# SIM_slots_2.net
KiCad netlist of a schematic drawn in Altium Designer
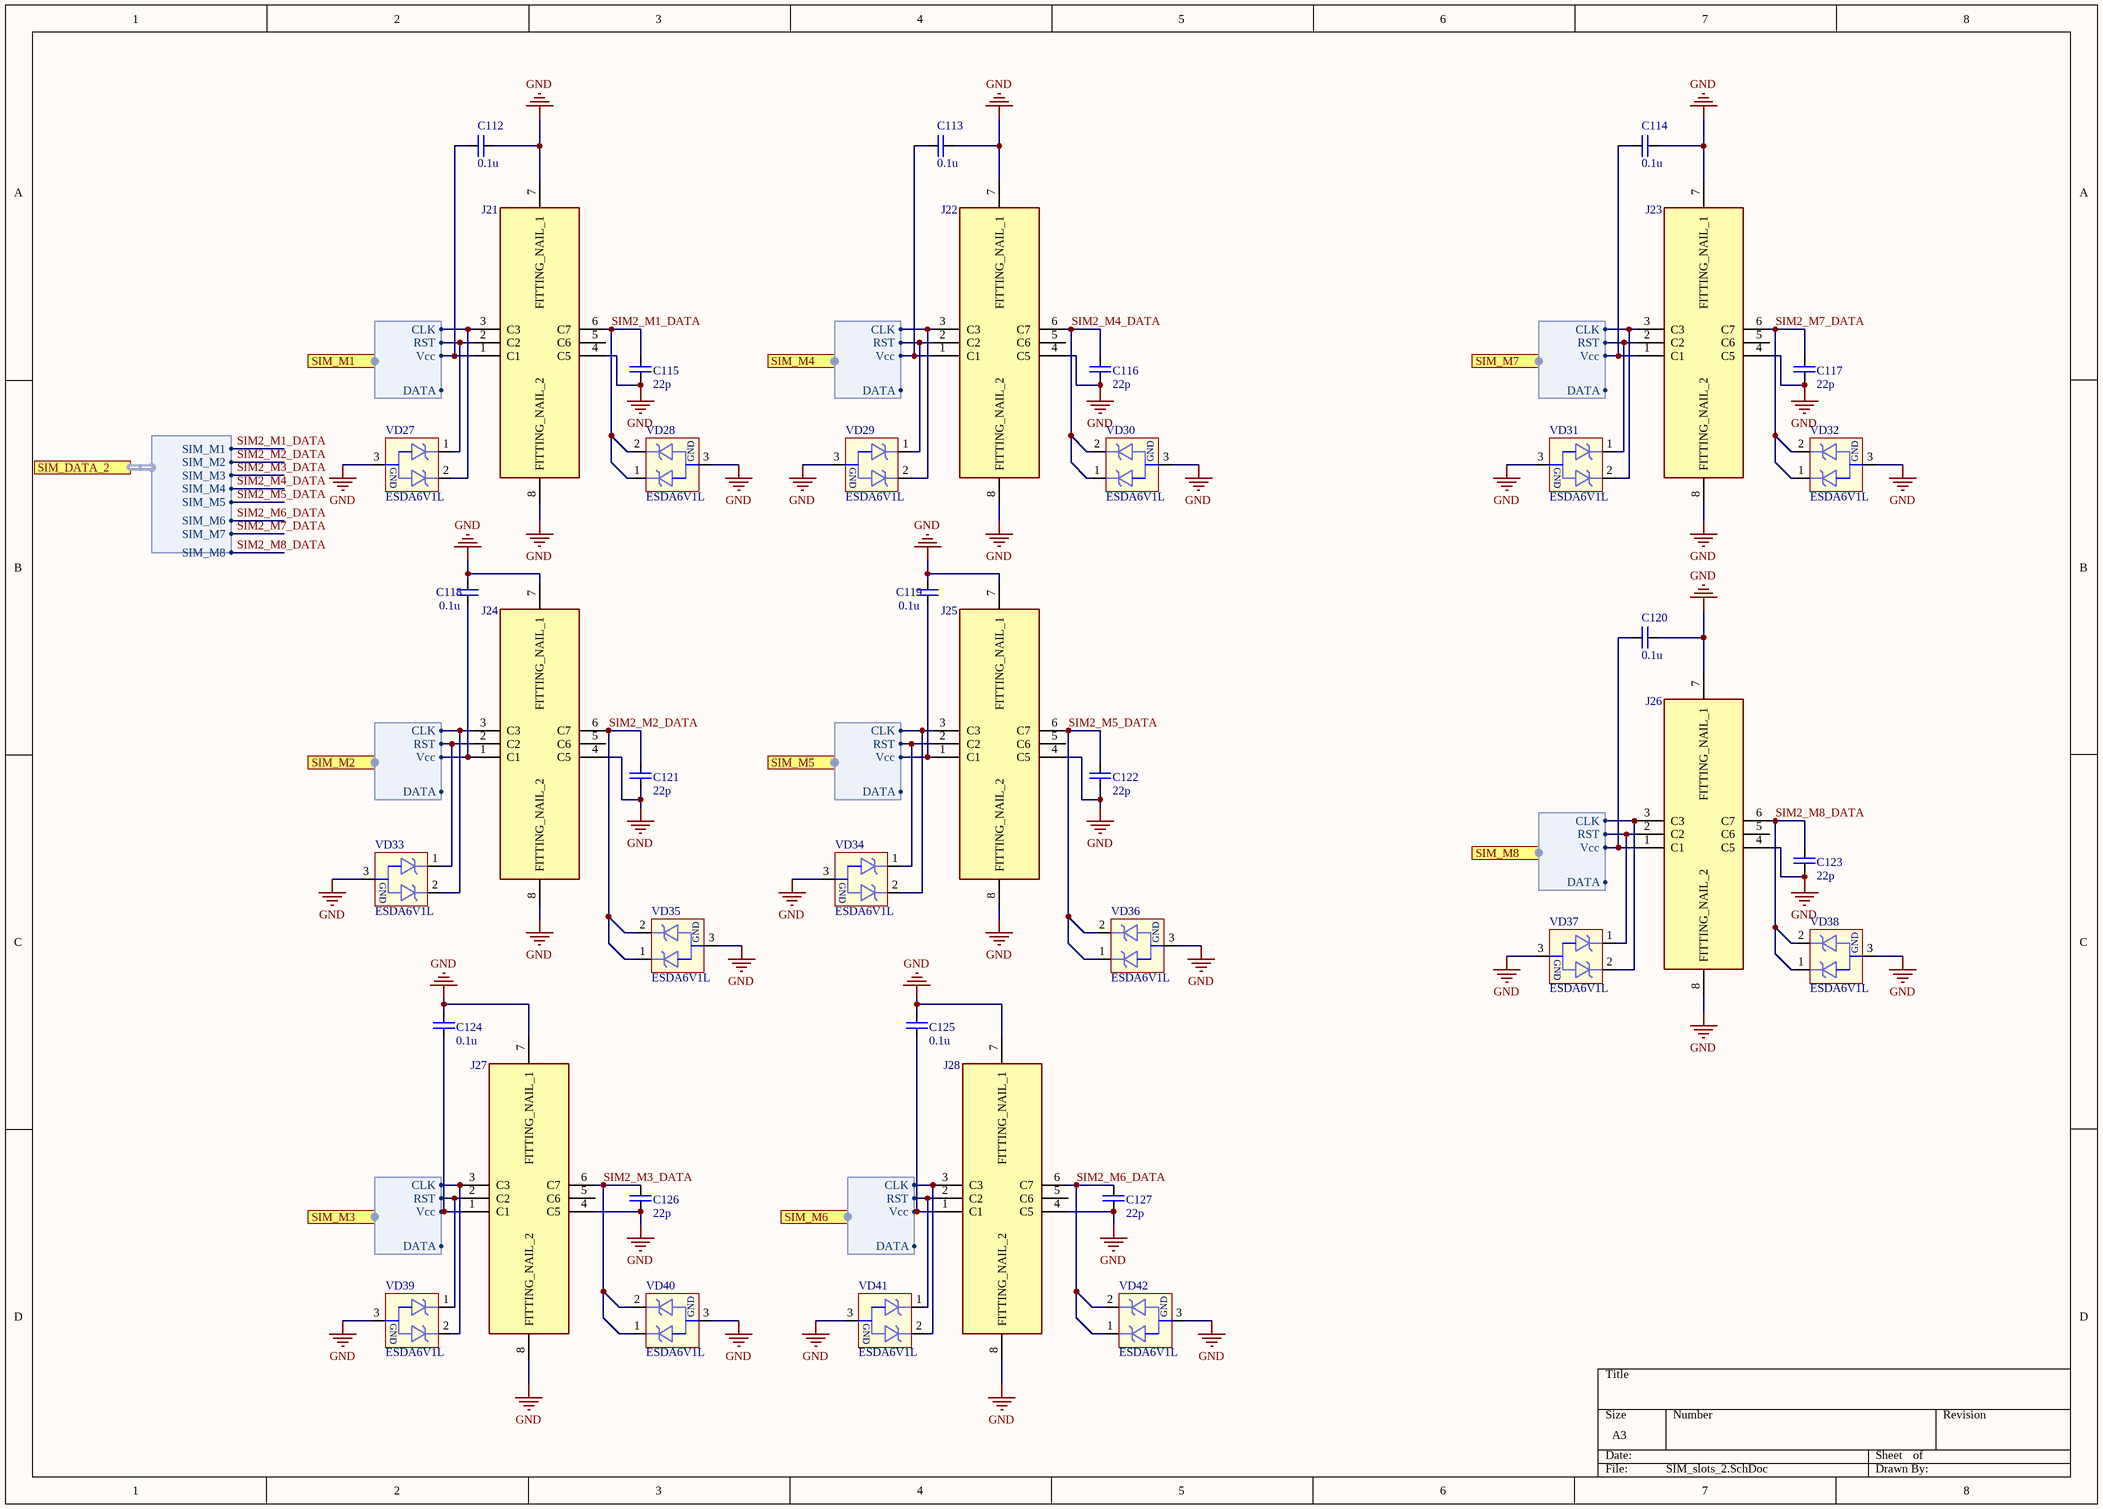
[diagram p0: SIM_slots_2.SchDoc]

(export (version "E")
  (design (tool "Eeschema 10.0.6"))
  (components
    (comp (ref "C112")
      (value "0.1u")
      (footprint "SMD_components:C0402")
      (description "Chip Capacitor 0402")
      (fields (field (name "TOLERANCE") "10%") (field (name "VOLTAGE") "25В"))
      (libsource (lib "Passives") (part "C0402"))
    )
    (comp (ref "C113")
      (value "0.1u")
      (footprint "SMD_components:C0402")
      (description "Chip Capacitor 0402")
      (fields (field (name "TOLERANCE") "10%") (field (name "VOLTAGE") "25В"))
      (libsource (lib "Passives") (part "C0402"))
    )
    (comp (ref "C114")
      (value "0.1u")
      (footprint "SMD_components:C0402")
      (description "Chip Capacitor 0402")
      (fields (field (name "TOLERANCE") "10%") (field (name "VOLTAGE") "25В"))
      (libsource (lib "Passives") (part "C0402"))
    )
    (comp (ref "C115")
      (value "22p")
      (footprint "SMD_components:C0402")
      (description "Chip Capacitor 0402")
      (fields (field (name "TOLERANCE") "10%") (field (name "VOLTAGE") "50В"))
      (libsource (lib "Passives") (part "C0402"))
    )
    (comp (ref "C116")
      (value "22p")
      (footprint "SMD_components:C0402")
      (description "Chip Capacitor 0402")
      (fields (field (name "TOLERANCE") "10%") (field (name "VOLTAGE") "50В"))
      (libsource (lib "Passives") (part "C0402"))
    )
    (comp (ref "C117")
      (value "22p")
      (footprint "SMD_components:C0402")
      (description "Chip Capacitor 0402")
      (fields (field (name "TOLERANCE") "10%") (field (name "VOLTAGE") "50В"))
      (libsource (lib "Passives") (part "C0402"))
    )
    (comp (ref "C118")
      (value "0.1u")
      (footprint "SMD_components:C0402")
      (description "Chip Capacitor 0402")
      (fields (field (name "TOLERANCE") "10%") (field (name "VOLTAGE") "25В"))
      (libsource (lib "Passives") (part "C0402"))
    )
    (comp (ref "C119")
      (value "0.1u")
      (footprint "SMD_components:C0402")
      (description "Chip Capacitor 0402")
      (fields (field (name "TOLERANCE") "10%") (field (name "VOLTAGE") "25В"))
      (libsource (lib "Passives") (part "C0402"))
    )
    (comp (ref "C120")
      (value "0.1u")
      (footprint "SMD_components:C0402")
      (description "Chip Capacitor 0402")
      (fields (field (name "TOLERANCE") "10%") (field (name "VOLTAGE") "25В"))
      (libsource (lib "Passives") (part "C0402"))
    )
    (comp (ref "C121")
      (value "22p")
      (footprint "SMD_components:C0402")
      (description "Chip Capacitor 0402")
      (fields (field (name "TOLERANCE") "10%") (field (name "VOLTAGE") "50В"))
      (libsource (lib "Passives") (part "C0402"))
    )
    (comp (ref "C122")
      (value "22p")
      (footprint "SMD_components:C0402")
      (description "Chip Capacitor 0402")
      (fields (field (name "TOLERANCE") "10%") (field (name "VOLTAGE") "50В"))
      (libsource (lib "Passives") (part "C0402"))
    )
    (comp (ref "C123")
      (value "22p")
      (footprint "SMD_components:C0402")
      (description "Chip Capacitor 0402")
      (fields (field (name "TOLERANCE") "10%") (field (name "VOLTAGE") "50В"))
      (libsource (lib "Passives") (part "C0402"))
    )
    (comp (ref "C124")
      (value "0.1u")
      (footprint "SMD_components:C0402")
      (description "Chip Capacitor 0402")
      (fields (field (name "TOLERANCE") "10%") (field (name "VOLTAGE") "25В"))
      (libsource (lib "Passives") (part "C0402"))
    )
    (comp (ref "C125")
      (value "0.1u")
      (footprint "SMD_components:C0402")
      (description "Chip Capacitor 0402")
      (fields (field (name "TOLERANCE") "10%") (field (name "VOLTAGE") "25В"))
      (libsource (lib "Passives") (part "C0402"))
    )
    (comp (ref "C126")
      (value "22p")
      (footprint "SMD_components:C0402")
      (description "Chip Capacitor 0402")
      (fields (field (name "TOLERANCE") "10%") (field (name "VOLTAGE") "50В"))
      (libsource (lib "Passives") (part "C0402"))
    )
    (comp (ref "C127")
      (value "22p")
      (footprint "SMD_components:C0402")
      (description "Chip Capacitor 0402")
      (fields (field (name "TOLERANCE") "10%") (field (name "VOLTAGE") "50В"))
      (libsource (lib "Passives") (part "C0402"))
    )
    (comp (ref "J21")
      (value "47388-2001")
      (footprint "473882001")
      (description "Connector")
      (fields (field (name "MOUSER PART NUMBER") "538-47388-2001"))
      (libsource (lib "Connectors") (part "47388-2001"))
    )
    (comp (ref "J22")
      (value "47388-2001")
      (footprint "473882001")
      (description "Connector")
      (fields (field (name "MOUSER PART NUMBER") "538-47388-2001"))
      (libsource (lib "Connectors") (part "47388-2001"))
    )
    (comp (ref "J23")
      (value "47388-2001")
      (footprint "473882001")
      (description "Connector")
      (fields (field (name "MOUSER PART NUMBER") "538-47388-2001"))
      (libsource (lib "Connectors") (part "47388-2001"))
    )
    (comp (ref "J24")
      (value "47388-2001")
      (footprint "473882001")
      (description "Connector")
      (fields (field (name "MOUSER PART NUMBER") "538-47388-2001"))
      (libsource (lib "Connectors") (part "47388-2001"))
    )
    (comp (ref "J25")
      (value "47388-2001")
      (footprint "473882001")
      (description "Connector")
      (fields (field (name "MOUSER PART NUMBER") "538-47388-2001"))
      (libsource (lib "Connectors") (part "47388-2001"))
    )
    (comp (ref "J26")
      (value "47388-2001")
      (footprint "473882001")
      (description "Connector")
      (fields (field (name "MOUSER PART NUMBER") "538-47388-2001"))
      (libsource (lib "Connectors") (part "47388-2001"))
    )
    (comp (ref "J27")
      (value "47388-2001")
      (footprint "473882001")
      (description "Connector")
      (fields (field (name "MOUSER PART NUMBER") "538-47388-2001"))
      (libsource (lib "Connectors") (part "47388-2001"))
    )
    (comp (ref "J28")
      (value "47388-2001")
      (footprint "473882001")
      (description "Connector")
      (fields (field (name "MOUSER PART NUMBER") "538-47388-2001"))
      (libsource (lib "Connectors") (part "47388-2001"))
    )
    (comp (ref "VD27")
      (value "Диод защитный, ESDA6V1L")
      (footprint "SMD_components:SOT23-3L")
      (description "Dual diode array for ESD protection")
      (fields (field (name "MANUFACTURER") "STMicroelectronics") (field (name "PARTNUMBER") "ESDA6V1L"))
      (libsource (lib "Discrete") (part "ESDA6V1L"))
    )
    (comp (ref "VD28")
      (value "Диод защитный, ESDA6V1L")
      (footprint "SMD_components:SOT23-3L")
      (description "Dual diode array for ESD protection")
      (fields (field (name "MANUFACTURER") "STMicroelectronics") (field (name "PARTNUMBER") "ESDA6V1L"))
      (libsource (lib "") (part "ESDA6V1L_1"))
    )
    (comp (ref "VD29")
      (value "Диод защитный, ESDA6V1L")
      (footprint "SMD_components:SOT23-3L")
      (description "Dual diode array for ESD protection")
      (fields (field (name "MANUFACTURER") "STMicroelectronics") (field (name "PARTNUMBER") "ESDA6V1L"))
      (libsource (lib "Discrete") (part "ESDA6V1L"))
    )
    (comp (ref "VD30")
      (value "Диод защитный, ESDA6V1L")
      (footprint "SMD_components:SOT23-3L")
      (description "Dual diode array for ESD protection")
      (fields (field (name "MANUFACTURER") "STMicroelectronics") (field (name "PARTNUMBER") "ESDA6V1L"))
      (libsource (lib "") (part "ESDA6V1L_1"))
    )
    (comp (ref "VD31")
      (value "Диод защитный, ESDA6V1L")
      (footprint "SMD_components:SOT23-3L")
      (description "Dual diode array for ESD protection")
      (fields (field (name "MANUFACTURER") "STMicroelectronics") (field (name "PARTNUMBER") "ESDA6V1L"))
      (libsource (lib "Discrete") (part "ESDA6V1L"))
    )
    (comp (ref "VD32")
      (value "Диод защитный, ESDA6V1L")
      (footprint "SMD_components:SOT23-3L")
      (description "Dual diode array for ESD protection")
      (fields (field (name "MANUFACTURER") "STMicroelectronics") (field (name "PARTNUMBER") "ESDA6V1L"))
      (libsource (lib "") (part "ESDA6V1L_1"))
    )
    (comp (ref "VD33")
      (value "Диод защитный, ESDA6V1L")
      (footprint "SMD_components:SOT23-3L")
      (description "Dual diode array for ESD protection")
      (fields (field (name "MANUFACTURER") "STMicroelectronics") (field (name "PARTNUMBER") "ESDA6V1L"))
      (libsource (lib "Discrete") (part "ESDA6V1L"))
    )
    (comp (ref "VD34")
      (value "Диод защитный, ESDA6V1L")
      (footprint "SMD_components:SOT23-3L")
      (description "Dual diode array for ESD protection")
      (fields (field (name "MANUFACTURER") "STMicroelectronics") (field (name "PARTNUMBER") "ESDA6V1L"))
      (libsource (lib "Discrete") (part "ESDA6V1L"))
    )
    (comp (ref "VD35")
      (value "Диод защитный, ESDA6V1L")
      (footprint "SMD_components:SOT23-3L")
      (description "Dual diode array for ESD protection")
      (fields (field (name "MANUFACTURER") "STMicroelectronics") (field (name "PARTNUMBER") "ESDA6V1L"))
      (libsource (lib "") (part "ESDA6V1L_1"))
    )
    (comp (ref "VD36")
      (value "Диод защитный, ESDA6V1L")
      (footprint "SMD_components:SOT23-3L")
      (description "Dual diode array for ESD protection")
      (fields (field (name "MANUFACTURER") "STMicroelectronics") (field (name "PARTNUMBER") "ESDA6V1L"))
      (libsource (lib "") (part "ESDA6V1L_1"))
    )
    (comp (ref "VD37")
      (value "Диод защитный, ESDA6V1L")
      (footprint "SMD_components:SOT23-3L")
      (description "Dual diode array for ESD protection")
      (fields (field (name "MANUFACTURER") "STMicroelectronics") (field (name "PARTNUMBER") "ESDA6V1L"))
      (libsource (lib "Discrete") (part "ESDA6V1L"))
    )
    (comp (ref "VD38")
      (value "Диод защитный, ESDA6V1L")
      (footprint "SMD_components:SOT23-3L")
      (description "Dual diode array for ESD protection")
      (fields (field (name "MANUFACTURER") "STMicroelectronics") (field (name "PARTNUMBER") "ESDA6V1L"))
      (libsource (lib "") (part "ESDA6V1L_1"))
    )
    (comp (ref "VD39")
      (value "Диод защитный, ESDA6V1L")
      (footprint "SMD_components:SOT23-3L")
      (description "Dual diode array for ESD protection")
      (fields (field (name "MANUFACTURER") "STMicroelectronics") (field (name "PARTNUMBER") "ESDA6V1L"))
      (libsource (lib "Discrete") (part "ESDA6V1L"))
    )
    (comp (ref "VD40")
      (value "Диод защитный, ESDA6V1L")
      (footprint "SMD_components:SOT23-3L")
      (description "Dual diode array for ESD protection")
      (fields (field (name "MANUFACTURER") "STMicroelectronics") (field (name "PARTNUMBER") "ESDA6V1L"))
      (libsource (lib "") (part "ESDA6V1L_1"))
    )
    (comp (ref "VD41")
      (value "Диод защитный, ESDA6V1L")
      (footprint "SMD_components:SOT23-3L")
      (description "Dual diode array for ESD protection")
      (fields (field (name "MANUFACTURER") "STMicroelectronics") (field (name "PARTNUMBER") "ESDA6V1L"))
      (libsource (lib "Discrete") (part "ESDA6V1L"))
    )
    (comp (ref "VD42")
      (value "Диод защитный, ESDA6V1L")
      (footprint "SMD_components:SOT23-3L")
      (description "Dual diode array for ESD protection")
      (fields (field (name "MANUFACTURER") "STMicroelectronics") (field (name "PARTNUMBER") "ESDA6V1L"))
      (libsource (lib "") (part "ESDA6V1L_1"))
    )
  )
  (nets
    (net (code "3") (name "/SIM2_M1_DATA") (class "Default")
      (node (ref "C115") (pin "2") (pinfunction "2_2") (pintype "passive"))
      (node (ref "J21") (pin "6") (pinfunction "C7_6") (pintype "passive"))
      (node (ref "VD28") (pin "1") (pinfunction "1_1") (pintype "passive"))
      (node (ref "VD28") (pin "2") (pinfunction "2_2") (pintype "passive"))
    )
    (net (code "4") (name "/SIM2_M2_DATA") (class "Default")
      (node (ref "C121") (pin "2") (pinfunction "2_2") (pintype "passive"))
      (node (ref "J24") (pin "6") (pinfunction "C7_6") (pintype "passive"))
      (node (ref "VD35") (pin "1") (pinfunction "1_1") (pintype "passive"))
      (node (ref "VD35") (pin "2") (pinfunction "2_2") (pintype "passive"))
    )
    (net (code "5") (name "/SIM2_M3_DATA") (class "Default")
      (node (ref "C126") (pin "2") (pinfunction "2_2") (pintype "passive"))
      (node (ref "J27") (pin "6") (pinfunction "C7_6") (pintype "passive"))
      (node (ref "VD40") (pin "1") (pinfunction "1_1") (pintype "passive"))
      (node (ref "VD40") (pin "2") (pinfunction "2_2") (pintype "passive"))
    )
    (net (code "6") (name "/SIM2_M4_DATA") (class "Default")
      (node (ref "C116") (pin "2") (pinfunction "2_2") (pintype "passive"))
      (node (ref "J22") (pin "6") (pinfunction "C7_6") (pintype "passive"))
      (node (ref "VD30") (pin "1") (pinfunction "1_1") (pintype "passive"))
      (node (ref "VD30") (pin "2") (pinfunction "2_2") (pintype "passive"))
    )
    (net (code "7") (name "/SIM2_M5_DATA") (class "Default")
      (node (ref "C122") (pin "2") (pinfunction "2_2") (pintype "passive"))
      (node (ref "J25") (pin "6") (pinfunction "C7_6") (pintype "passive"))
      (node (ref "VD36") (pin "1") (pinfunction "1_1") (pintype "passive"))
      (node (ref "VD36") (pin "2") (pinfunction "2_2") (pintype "passive"))
    )
    (net (code "8") (name "/SIM2_M6_DATA") (class "Default")
      (node (ref "C127") (pin "2") (pinfunction "2_2") (pintype "passive"))
      (node (ref "J28") (pin "6") (pinfunction "C7_6") (pintype "passive"))
      (node (ref "VD42") (pin "1") (pinfunction "1_1") (pintype "passive"))
      (node (ref "VD42") (pin "2") (pinfunction "2_2") (pintype "passive"))
    )
    (net (code "9") (name "/SIM2_M7_DATA") (class "Default")
      (node (ref "C117") (pin "2") (pinfunction "2_2") (pintype "passive"))
      (node (ref "J23") (pin "6") (pinfunction "C7_6") (pintype "passive"))
      (node (ref "VD32") (pin "1") (pinfunction "1_1") (pintype "passive"))
      (node (ref "VD32") (pin "2") (pinfunction "2_2") (pintype "passive"))
    )
    (net (code "10") (name "/SIM2_M8_DATA") (class "Default")
      (node (ref "C123") (pin "2") (pinfunction "2_2") (pintype "passive"))
      (node (ref "J26") (pin "6") (pinfunction "C7_6") (pintype "passive"))
      (node (ref "VD38") (pin "1") (pinfunction "1_1") (pintype "passive"))
      (node (ref "VD38") (pin "2") (pinfunction "2_2") (pintype "passive"))
    )
    (net (code "13") (name "GND") (class "Default")
      (node (ref "C112") (pin "2") (pinfunction "2_2") (pintype "passive"))
      (node (ref "C113") (pin "2") (pinfunction "2_2") (pintype "passive"))
      (node (ref "C114") (pin "2") (pinfunction "2_2") (pintype "passive"))
      (node (ref "C115") (pin "1") (pinfunction "1_1") (pintype "passive"))
      (node (ref "C116") (pin "1") (pinfunction "1_1") (pintype "passive"))
      (node (ref "C117") (pin "1") (pinfunction "1_1") (pintype "passive"))
      (node (ref "C118") (pin "2") (pinfunction "2_2") (pintype "passive"))
      (node (ref "C119") (pin "2") (pinfunction "2_2") (pintype "passive"))
      (node (ref "C120") (pin "2") (pinfunction "2_2") (pintype "passive"))
      (node (ref "C121") (pin "1") (pinfunction "1_1") (pintype "passive"))
      (node (ref "C122") (pin "1") (pinfunction "1_1") (pintype "passive"))
      (node (ref "C123") (pin "1") (pinfunction "1_1") (pintype "passive"))
      (node (ref "C124") (pin "2") (pinfunction "2_2") (pintype "passive"))
      (node (ref "C125") (pin "2") (pinfunction "2_2") (pintype "passive"))
      (node (ref "C126") (pin "1") (pinfunction "1_1") (pintype "passive"))
      (node (ref "C127") (pin "1") (pinfunction "1_1") (pintype "passive"))
      (node (ref "J21") (pin "4") (pinfunction "C5_4") (pintype "passive"))
      (node (ref "J21") (pin "7") (pinfunction "FITTING_NAIL_1_7") (pintype "passive"))
      (node (ref "J21") (pin "8") (pinfunction "FITTING_NAIL_2_8") (pintype "passive"))
      (node (ref "J22") (pin "4") (pinfunction "C5_4") (pintype "passive"))
      (node (ref "J22") (pin "7") (pinfunction "FITTING_NAIL_1_7") (pintype "passive"))
      (node (ref "J22") (pin "8") (pinfunction "FITTING_NAIL_2_8") (pintype "passive"))
      (node (ref "J23") (pin "4") (pinfunction "C5_4") (pintype "passive"))
      (node (ref "J23") (pin "7") (pinfunction "FITTING_NAIL_1_7") (pintype "passive"))
      (node (ref "J23") (pin "8") (pinfunction "FITTING_NAIL_2_8") (pintype "passive"))
      (node (ref "J24") (pin "4") (pinfunction "C5_4") (pintype "passive"))
      (node (ref "J24") (pin "7") (pinfunction "FITTING_NAIL_1_7") (pintype "passive"))
      (node (ref "J24") (pin "8") (pinfunction "FITTING_NAIL_2_8") (pintype "passive"))
      (node (ref "J25") (pin "4") (pinfunction "C5_4") (pintype "passive"))
      (node (ref "J25") (pin "7") (pinfunction "FITTING_NAIL_1_7") (pintype "passive"))
      (node (ref "J25") (pin "8") (pinfunction "FITTING_NAIL_2_8") (pintype "passive"))
      (node (ref "J26") (pin "4") (pinfunction "C5_4") (pintype "passive"))
      (node (ref "J26") (pin "7") (pinfunction "FITTING_NAIL_1_7") (pintype "passive"))
      (node (ref "J26") (pin "8") (pinfunction "FITTING_NAIL_2_8") (pintype "passive"))
      (node (ref "J27") (pin "4") (pinfunction "C5_4") (pintype "passive"))
      (node (ref "J27") (pin "7") (pinfunction "FITTING_NAIL_1_7") (pintype "passive"))
      (node (ref "J27") (pin "8") (pinfunction "FITTING_NAIL_2_8") (pintype "passive"))
      (node (ref "J28") (pin "4") (pinfunction "C5_4") (pintype "passive"))
      (node (ref "J28") (pin "7") (pinfunction "FITTING_NAIL_1_7") (pintype "passive"))
      (node (ref "J28") (pin "8") (pinfunction "FITTING_NAIL_2_8") (pintype "passive"))
      (node (ref "VD27") (pin "3") (pinfunction "GND_3") (pintype "passive"))
      (node (ref "VD28") (pin "3") (pinfunction "GND_3") (pintype "passive"))
      (node (ref "VD29") (pin "3") (pinfunction "GND_3") (pintype "passive"))
      (node (ref "VD30") (pin "3") (pinfunction "GND_3") (pintype "passive"))
      (node (ref "VD31") (pin "3") (pinfunction "GND_3") (pintype "passive"))
      (node (ref "VD32") (pin "3") (pinfunction "GND_3") (pintype "passive"))
      (node (ref "VD33") (pin "3") (pinfunction "GND_3") (pintype "passive"))
      (node (ref "VD34") (pin "3") (pinfunction "GND_3") (pintype "passive"))
      (node (ref "VD35") (pin "3") (pinfunction "GND_3") (pintype "passive"))
      (node (ref "VD36") (pin "3") (pinfunction "GND_3") (pintype "passive"))
      (node (ref "VD37") (pin "3") (pinfunction "GND_3") (pintype "passive"))
      (node (ref "VD38") (pin "3") (pinfunction "GND_3") (pintype "passive"))
      (node (ref "VD39") (pin "3") (pinfunction "GND_3") (pintype "passive"))
      (node (ref "VD40") (pin "3") (pinfunction "GND_3") (pintype "passive"))
      (node (ref "VD41") (pin "3") (pinfunction "GND_3") (pintype "passive"))
      (node (ref "VD42") (pin "3") (pinfunction "GND_3") (pintype "passive"))
    )
    (net (code "14") (name "Net-(J21-C1)") (class "Default")
      (node (ref "C112") (pin "1") (pinfunction "1_1") (pintype "passive"))
      (node (ref "J21") (pin "1") (pinfunction "C1_1") (pintype "passive"))
    )
    (net (code "15") (name "Net-(J21-C2)") (class "Default")
      (node (ref "J21") (pin "2") (pinfunction "C2_2") (pintype "passive"))
      (node (ref "VD27") (pin "1") (pinfunction "1_1") (pintype "passive"))
    )
    (net (code "16") (name "Net-(J21-C3)") (class "Default")
      (node (ref "J21") (pin "3") (pinfunction "C3_3") (pintype "passive"))
      (node (ref "VD27") (pin "2") (pinfunction "2_2") (pintype "passive"))
    )
    (net (code "17") (name "Net-(J22-C1)") (class "Default")
      (node (ref "C113") (pin "1") (pinfunction "1_1") (pintype "passive"))
      (node (ref "J22") (pin "1") (pinfunction "C1_1") (pintype "passive"))
    )
    (net (code "18") (name "Net-(J22-C2)") (class "Default")
      (node (ref "J22") (pin "2") (pinfunction "C2_2") (pintype "passive"))
      (node (ref "VD29") (pin "1") (pinfunction "1_1") (pintype "passive"))
    )
    (net (code "19") (name "Net-(J22-C3)") (class "Default")
      (node (ref "J22") (pin "3") (pinfunction "C3_3") (pintype "passive"))
      (node (ref "VD29") (pin "2") (pinfunction "2_2") (pintype "passive"))
    )
    (net (code "20") (name "Net-(J23-C1)") (class "Default")
      (node (ref "C114") (pin "1") (pinfunction "1_1") (pintype "passive"))
      (node (ref "J23") (pin "1") (pinfunction "C1_1") (pintype "passive"))
    )
    (net (code "21") (name "Net-(J23-C2)") (class "Default")
      (node (ref "J23") (pin "2") (pinfunction "C2_2") (pintype "passive"))
      (node (ref "VD31") (pin "1") (pinfunction "1_1") (pintype "passive"))
    )
    (net (code "22") (name "Net-(J23-C3)") (class "Default")
      (node (ref "J23") (pin "3") (pinfunction "C3_3") (pintype "passive"))
      (node (ref "VD31") (pin "2") (pinfunction "2_2") (pintype "passive"))
    )
    (net (code "23") (name "Net-(J24-C1)") (class "Default")
      (node (ref "C118") (pin "1") (pinfunction "1_1") (pintype "passive"))
      (node (ref "J24") (pin "1") (pinfunction "C1_1") (pintype "passive"))
    )
    (net (code "24") (name "Net-(J24-C2)") (class "Default")
      (node (ref "J24") (pin "2") (pinfunction "C2_2") (pintype "passive"))
      (node (ref "VD33") (pin "1") (pinfunction "1_1") (pintype "passive"))
    )
    (net (code "25") (name "Net-(J24-C3)") (class "Default")
      (node (ref "J24") (pin "3") (pinfunction "C3_3") (pintype "passive"))
      (node (ref "VD33") (pin "2") (pinfunction "2_2") (pintype "passive"))
    )
    (net (code "26") (name "Net-(J25-C1)") (class "Default")
      (node (ref "C119") (pin "1") (pinfunction "1_1") (pintype "passive"))
      (node (ref "J25") (pin "1") (pinfunction "C1_1") (pintype "passive"))
    )
    (net (code "27") (name "Net-(J25-C2)") (class "Default")
      (node (ref "J25") (pin "2") (pinfunction "C2_2") (pintype "passive"))
      (node (ref "VD34") (pin "1") (pinfunction "1_1") (pintype "passive"))
    )
    (net (code "28") (name "Net-(J25-C3)") (class "Default")
      (node (ref "J25") (pin "3") (pinfunction "C3_3") (pintype "passive"))
      (node (ref "VD34") (pin "2") (pinfunction "2_2") (pintype "passive"))
    )
    (net (code "29") (name "Net-(J26-C1)") (class "Default")
      (node (ref "C120") (pin "1") (pinfunction "1_1") (pintype "passive"))
      (node (ref "J26") (pin "1") (pinfunction "C1_1") (pintype "passive"))
    )
    (net (code "30") (name "Net-(J26-C2)") (class "Default")
      (node (ref "J26") (pin "2") (pinfunction "C2_2") (pintype "passive"))
      (node (ref "VD37") (pin "1") (pinfunction "1_1") (pintype "passive"))
    )
    (net (code "31") (name "Net-(J26-C3)") (class "Default")
      (node (ref "J26") (pin "3") (pinfunction "C3_3") (pintype "passive"))
      (node (ref "VD37") (pin "2") (pinfunction "2_2") (pintype "passive"))
    )
    (net (code "32") (name "Net-(J27-C1)") (class "Default")
      (node (ref "C124") (pin "1") (pinfunction "1_1") (pintype "passive"))
      (node (ref "J27") (pin "1") (pinfunction "C1_1") (pintype "passive"))
    )
    (net (code "33") (name "Net-(J27-C2)") (class "Default")
      (node (ref "J27") (pin "2") (pinfunction "C2_2") (pintype "passive"))
      (node (ref "VD39") (pin "1") (pinfunction "1_1") (pintype "passive"))
    )
    (net (code "34") (name "Net-(J27-C3)") (class "Default")
      (node (ref "J27") (pin "3") (pinfunction "C3_3") (pintype "passive"))
      (node (ref "VD39") (pin "2") (pinfunction "2_2") (pintype "passive"))
    )
    (net (code "35") (name "Net-(J28-C1)") (class "Default")
      (node (ref "C125") (pin "1") (pinfunction "1_1") (pintype "passive"))
      (node (ref "J28") (pin "1") (pinfunction "C1_1") (pintype "passive"))
    )
    (net (code "36") (name "Net-(J28-C2)") (class "Default")
      (node (ref "J28") (pin "2") (pinfunction "C2_2") (pintype "passive"))
      (node (ref "VD41") (pin "1") (pinfunction "1_1") (pintype "passive"))
    )
    (net (code "37") (name "Net-(J28-C3)") (class "Default")
      (node (ref "J28") (pin "3") (pinfunction "C3_3") (pintype "passive"))
      (node (ref "VD41") (pin "2") (pinfunction "2_2") (pintype "passive"))
    )
    (net (code "38") (name "unconnected-(J21-C6-Pad5)") (class "Default")
      (node (ref "J21") (pin "5") (pinfunction "C6_5") (pintype "passive"))
    )
    (net (code "39") (name "unconnected-(J22-C6-Pad5)") (class "Default")
      (node (ref "J22") (pin "5") (pinfunction "C6_5") (pintype "passive"))
    )
    (net (code "40") (name "unconnected-(J23-C6-Pad5)") (class "Default")
      (node (ref "J23") (pin "5") (pinfunction "C6_5") (pintype "passive"))
    )
    (net (code "41") (name "unconnected-(J24-C6-Pad5)") (class "Default")
      (node (ref "J24") (pin "5") (pinfunction "C6_5") (pintype "passive"))
    )
    (net (code "42") (name "unconnected-(J25-C6-Pad5)") (class "Default")
      (node (ref "J25") (pin "5") (pinfunction "C6_5") (pintype "passive"))
    )
    (net (code "43") (name "unconnected-(J26-C6-Pad5)") (class "Default")
      (node (ref "J26") (pin "5") (pinfunction "C6_5") (pintype "passive"))
    )
    (net (code "44") (name "unconnected-(J27-C6-Pad5)") (class "Default")
      (node (ref "J27") (pin "5") (pinfunction "C6_5") (pintype "passive"))
    )
    (net (code "45") (name "unconnected-(J28-C6-Pad5)") (class "Default")
      (node (ref "J28") (pin "5") (pinfunction "C6_5") (pintype "passive"))
    )
  )
)
